# XIAO-log_2.net
KiCad netlist of a schematic drawn in Altium Designer
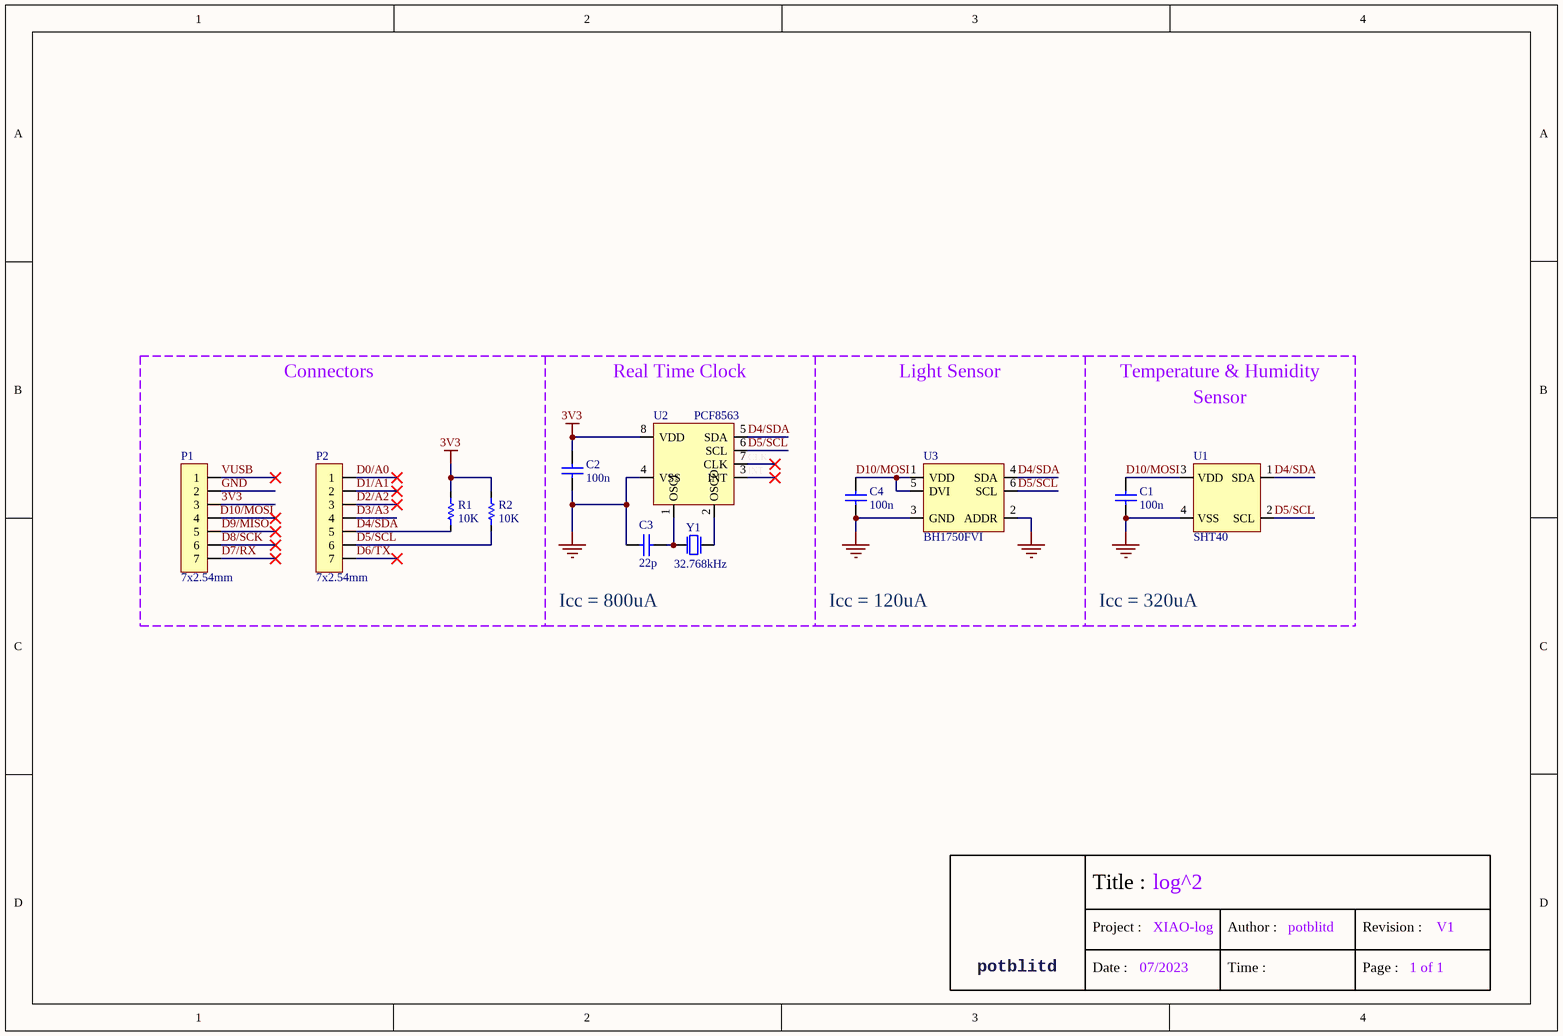
[diagram p0: XIAO-log^2.SchDoc]

(export (version "E")
  (design (tool "Eeschema 10.0.6"))
  (components
    (comp (ref "C1")
      (value "100n")
      (footprint "0603C")
      (description "Capacitor 100nF ±10% 50V")
      (fields (field (name "Comment") "Capacitor"))
      (libsource (lib "Simulation Generic Components") (part "Capacitor"))
    )
    (comp (ref "C2")
      (value "100n")
      (footprint "0603C")
      (description "Capacitor 100nF ±10% 50V")
      (fields (field (name "Comment") "Capacitor"))
      (libsource (lib "Simulation Generic Components") (part "Capacitor"))
    )
    (comp (ref "C3")
      (value "22p")
      (footprint "0603C")
      (description "Capacitor 22pF ±5% 50V")
      (fields (field (name "Comment") "Capacitor"))
      (libsource (lib "Simulation Generic Components") (part "Capacitor"))
    )
    (comp (ref "C4")
      (value "100n")
      (footprint "0603C")
      (description "Capacitor 100nF ±10% 50V")
      (fields (field (name "Comment") "Capacitor"))
      (libsource (lib "Simulation Generic Components") (part "Capacitor"))
    )
    (comp (ref "P1")
      (value "7x2.54mm")
      (footprint "7P-2.54mm-0.84")
      (description "General 7-pin connection")
      (libsource (lib "AltiumLib") (part "7-pins Header"))
    )
    (comp (ref "P2")
      (value "7x2.54mm")
      (footprint "7P-2.54mm-0.84")
      (description "General 7-pin connection")
      (libsource (lib "AltiumLib") (part "7-pins Header"))
    )
    (comp (ref "R1")
      (value "10K")
      (footprint "0603R")
      (description "Resistor 10kΩ ±1% 1/16W")
      (fields (field (name "Comment") "Resistor"))
      (libsource (lib "Simulation Generic Components") (part "RES"))
    )
    (comp (ref "R2")
      (value "10K")
      (footprint "0603R")
      (description "Resistor 10kΩ ±1% 1/16W")
      (fields (field (name "Comment") "Resistor"))
      (libsource (lib "Simulation Generic Components") (part "RES"))
    )
    (comp (ref "U1")
      (value "SHT40")
      (footprint "DFN-4-EP(1.5x1.5)")
      (description "SHT40 temperature and humidity sensor")
      (libsource (lib "AltiumLib") (part "SHT40"))
    )
    (comp (ref "U2")
      (value "PCF8563")
      (footprint "SOP-8")
      (description "IC real-time clock with alarm interrupt")
      (libsource (lib "AltiumLib") (part "RTC-8563"))
    )
    (comp (ref "U3")
      (value "BH1750FVI")
      (footprint "WSOF6")
      (description "Digital light sensor")
      (libsource (lib "AltiumLib") (part "BH1750"))
    )
    (comp (ref "Y1")
      (value "32.768kHz")
      (footprint "FC135")
      (description "Crystal oscillator 32.768kHz 20ppm 12.5pF")
      (fields (field (name "Comment") "Oscillator"))
      (libsource (lib "AltiumLib") (part "XO-2"))
    )
  )
  (nets
    (net (code "1") (name "/CLK") (class "Default")
      (node (ref "U2") (pin "7") (pinfunction "CLK_7") (pintype "passive+no_connect"))
    )
    (net (code "2") (name "/D0{slash}A0") (class "Default")
      (node (ref "P2") (pin "1") (pinfunction "1_1") (pintype "passive+no_connect"))
    )
    (net (code "3") (name "/D1{slash}A1") (class "Default")
      (node (ref "P2") (pin "2") (pinfunction "2_2") (pintype "passive+no_connect"))
    )
    (net (code "4") (name "/D2{slash}A2") (class "Default")
      (node (ref "P2") (pin "3") (pinfunction "3_3") (pintype "passive+no_connect"))
    )
    (net (code "5") (name "/D3{slash}A3") (class "Default")
      (node (ref "P2") (pin "4") (pinfunction "4_4") (pintype "passive"))
    )
    (net (code "6") (name "/D4{slash}SDA") (class "Default")
      (node (ref "P2") (pin "5") (pinfunction "5_5") (pintype "passive"))
      (node (ref "R1") (pin "1") (pinfunction "1_1") (pintype "passive"))
      (node (ref "U1") (pin "1") (pinfunction "SDA_1") (pintype "passive"))
      (node (ref "U2") (pin "5") (pinfunction "SDA_5") (pintype "passive"))
      (node (ref "U3") (pin "4") (pinfunction "SDA_4") (pintype "passive"))
    )
    (net (code "7") (name "/D5{slash}SCL") (class "Default")
      (node (ref "P2") (pin "6") (pinfunction "6_6") (pintype "passive"))
      (node (ref "R2") (pin "1") (pinfunction "1_1") (pintype "passive"))
      (node (ref "U1") (pin "2") (pinfunction "SCL_2") (pintype "passive"))
      (node (ref "U2") (pin "6") (pinfunction "SCL_6") (pintype "passive"))
      (node (ref "U3") (pin "6") (pinfunction "SCL_6") (pintype "passive"))
    )
    (net (code "8") (name "/D6{slash}TX") (class "Default")
      (node (ref "P2") (pin "7") (pinfunction "7_7") (pintype "passive+no_connect"))
    )
    (net (code "9") (name "/D7{slash}RX") (class "Default")
      (node (ref "P1") (pin "7") (pinfunction "7_7") (pintype "passive+no_connect"))
    )
    (net (code "10") (name "/D8{slash}SCK") (class "Default")
      (node (ref "P1") (pin "6") (pinfunction "6_6") (pintype "passive+no_connect"))
    )
    (net (code "11") (name "/D9{slash}MISO") (class "Default")
      (node (ref "P1") (pin "5") (pinfunction "5_5") (pintype "passive+no_connect"))
    )
    (net (code "12") (name "/D10{slash}MOSI") (class "Default")
      (node (ref "C1") (pin "1") (pinfunction "1_1") (pintype "passive"))
      (node (ref "C4") (pin "1") (pinfunction "1_1") (pintype "passive"))
      (node (ref "P1") (pin "4") (pinfunction "4_4") (pintype "passive"))
      (node (ref "U1") (pin "3") (pinfunction "VDD_3") (pintype "passive"))
      (node (ref "U3") (pin "1") (pinfunction "VDD_1") (pintype "passive"))
      (node (ref "U3") (pin "5") (pinfunction "DVI_5") (pintype "passive"))
    )
    (net (code "13") (name "/INT") (class "Default")
      (node (ref "U2") (pin "3") (pinfunction "INT_3") (pintype "passive+no_connect"))
    )
    (net (code "14") (name "/VUSB") (class "Default")
      (node (ref "P1") (pin "1") (pinfunction "1_1") (pintype "passive+no_connect"))
    )
    (net (code "15") (name "3V3") (class "Default")
      (node (ref "C2") (pin "1") (pinfunction "1_1") (pintype "passive"))
      (node (ref "P1") (pin "3") (pinfunction "3_3") (pintype "passive"))
      (node (ref "R1") (pin "2") (pinfunction "2_2") (pintype "passive"))
      (node (ref "R2") (pin "2") (pinfunction "2_2") (pintype "passive"))
      (node (ref "U2") (pin "8") (pinfunction "VDD_8") (pintype "passive"))
    )
    (net (code "16") (name "GND") (class "Default")
      (node (ref "C1") (pin "2") (pinfunction "2_2") (pintype "passive"))
      (node (ref "C2") (pin "2") (pinfunction "2_2") (pintype "passive"))
      (node (ref "C3") (pin "2") (pinfunction "2_2") (pintype "passive"))
      (node (ref "C4") (pin "2") (pinfunction "2_2") (pintype "passive"))
      (node (ref "P1") (pin "2") (pinfunction "2_2") (pintype "passive"))
      (node (ref "U1") (pin "4") (pinfunction "VSS_4") (pintype "passive"))
      (node (ref "U2") (pin "4") (pinfunction "VSS_4") (pintype "passive"))
      (node (ref "U3") (pin "2") (pinfunction "ADDR_2") (pintype "passive"))
      (node (ref "U3") (pin "3") (pinfunction "GND_3") (pintype "passive"))
    )
    (net (code "17") (name "Net-(U2-OSCI)") (class "Default")
      (node (ref "C3") (pin "1") (pinfunction "1_1") (pintype "passive"))
      (node (ref "U2") (pin "1") (pinfunction "OSCI_1") (pintype "passive"))
      (node (ref "Y1") (pin "2") (pinfunction "2_2") (pintype "passive"))
    )
    (net (code "18") (name "Net-(U2-OSCO)") (class "Default")
      (node (ref "U2") (pin "2") (pinfunction "OSCO_2") (pintype "passive"))
      (node (ref "Y1") (pin "1") (pinfunction "1_1") (pintype "passive"))
    )
  )
)
